# RF_LoRa___GPS.net
KiCad netlist of a schematic drawn in Altium Designer
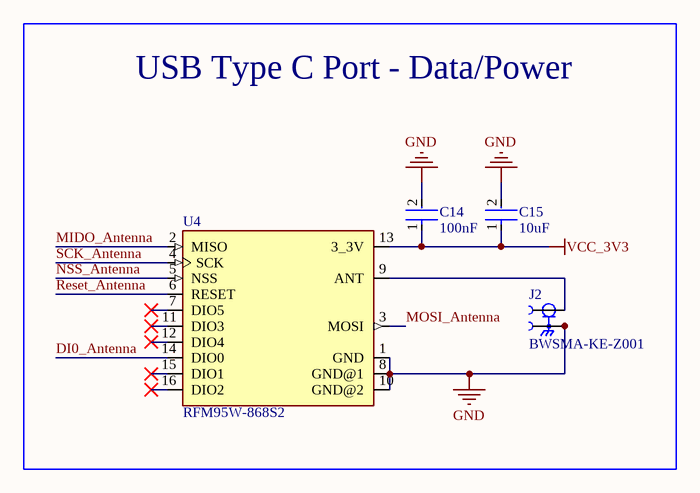
[diagram p0: RF_LoRa_&_GPS.SchDoc]

(export (version "E")
  (design (tool "Eeschema 10.0.6"))
  (components
    (comp (ref "C14")
      (value "100nF")
      (footprint "FP-C0805C-DN-MFG")
      (description "CAP CER 0.1UF 50V X7R 0805")
      (fields
        (field (name "MANUFACTURER PART NUMBER") "C0805C104K5RACTU")
        (field (name "MANUFACTURER") "KEMET")
      )
      (libsource (lib "Altium Content Vault") (part "b4654b650e69147ec39a6b967a45e02"))
    )
    (comp (ref "C15")
      (value "10uF")
      (footprint "FP-C0805C-DN-MFG")
      (description "CAP CER 0.1UF 50V X7R 0805")
      (fields
        (field (name "MANUFACTURER PART NUMBER") "C0805C104K5RACTU")
        (field (name "MANUFACTURER") "KEMET")
      )
      (libsource (lib "Altium Content Vault") (part "b4654b650e69147ec39a6b967a45e02"))
    )
    (comp (ref "J2")
      (value "BWSMA-KE-Z001")
      (footprint "BAT_WIRELESS_BWSMA-KE-Z001")
      (fields (field (name "MF") "Bat Wireless"))
      (libsource (lib "SMA") (part "BWSMA-KE-Z001"))
    )
    (comp (ref "U4")
      (value "RFM95W-868S2")
      (footprint "XCVR_RFM95W-868S2")
      (description "General ISM < 1GHz LoRaâ„¢ Transceiver Module 868MHz Antenna Not Included Surface Mount")
      (fields (field (name "MF") "RF"))
      (libsource (lib "Antenna-RFM95W-868S2") (part "RFM95W-868S2"))
    )
  )
  (nets
    (net (code "1") (name "/DI0_Antenna") (class "Default")
      (node (ref "U4") (pin "14") (pinfunction "DIO0_14") (pintype "bidirectional"))
    )
    (net (code "2") (name "/MIDO_Antenna") (class "Default")
      (node (ref "U4") (pin "2") (pinfunction "MISO_2") (pintype "input"))
    )
    (net (code "3") (name "/MOSI_Antenna") (class "Default")
      (node (ref "U4") (pin "3") (pinfunction "MOSI_3") (pintype "output"))
    )
    (net (code "4") (name "/NSS_Antenna") (class "Default")
      (node (ref "U4") (pin "5") (pinfunction "NSS_5") (pintype "input"))
    )
    (net (code "5") (name "/Reset_Antenna") (class "Default")
      (node (ref "U4") (pin "6") (pinfunction "RESET_6") (pintype "bidirectional"))
    )
    (net (code "6") (name "/SCK_Antenna") (class "Default")
      (node (ref "U4") (pin "4") (pinfunction "SCK_4") (pintype "input"))
    )
    (net (code "7") (name "GND") (class "Default")
      (node (ref "C14") (pin "2") (pinfunction "2_2") (pintype "passive"))
      (node (ref "C15") (pin "2") (pinfunction "2_2") (pintype "passive"))
      (node (ref "J2") (pin "2_1") (pinfunction "2_2_1") (pintype "passive"))
      (node (ref "J2") (pin "2_2") (pinfunction "2_2_2") (pintype "passive"))
      (node (ref "J2") (pin "2_3") (pinfunction "2_2_3") (pintype "passive"))
      (node (ref "J2") (pin "2_4") (pinfunction "2_2_4") (pintype "passive"))
      (node (ref "U4") (pin "1") (pinfunction "GND_1") (pintype "power_in"))
      (node (ref "U4") (pin "10") (pinfunction "GND@2_10") (pintype "power_in"))
      (node (ref "U4") (pin "8") (pinfunction "GND@1_8") (pintype "power_in"))
    )
    (net (code "8") (name "Net-(U4-ANT)") (class "Default")
      (node (ref "J2") (pin "1") (pinfunction "1_1") (pintype "passive"))
      (node (ref "U4") (pin "9") (pinfunction "ANT_9") (pintype "passive"))
    )
    (net (code "9") (name "VCC_3V3") (class "Default")
      (node (ref "C14") (pin "1") (pinfunction "1_1") (pintype "passive"))
      (node (ref "C15") (pin "1") (pinfunction "1_1") (pintype "passive"))
      (node (ref "U4") (pin "13") (pinfunction "3_3V_13") (pintype "power_in"))
    )
    (net (code "10") (name "unconnected-(U4-DIO1-Pad15)") (class "Default")
      (node (ref "U4") (pin "15") (pinfunction "DIO1_15") (pintype "bidirectional+no_connect"))
    )
    (net (code "11") (name "unconnected-(U4-DIO2-Pad16)") (class "Default")
      (node (ref "U4") (pin "16") (pinfunction "DIO2_16") (pintype "bidirectional+no_connect"))
    )
    (net (code "12") (name "unconnected-(U4-DIO3-Pad11)") (class "Default")
      (node (ref "U4") (pin "11") (pinfunction "DIO3_11") (pintype "bidirectional+no_connect"))
    )
    (net (code "13") (name "unconnected-(U4-DIO4-Pad12)") (class "Default")
      (node (ref "U4") (pin "12") (pinfunction "DIO4_12") (pintype "bidirectional+no_connect"))
    )
    (net (code "14") (name "unconnected-(U4-DIO5-Pad7)") (class "Default")
      (node (ref "U4") (pin "7") (pinfunction "DIO5_7") (pintype "bidirectional+no_connect"))
    )
  )
)
